# data_proV1_2.net
KiCad netlist of a schematic drawn in EAGLE
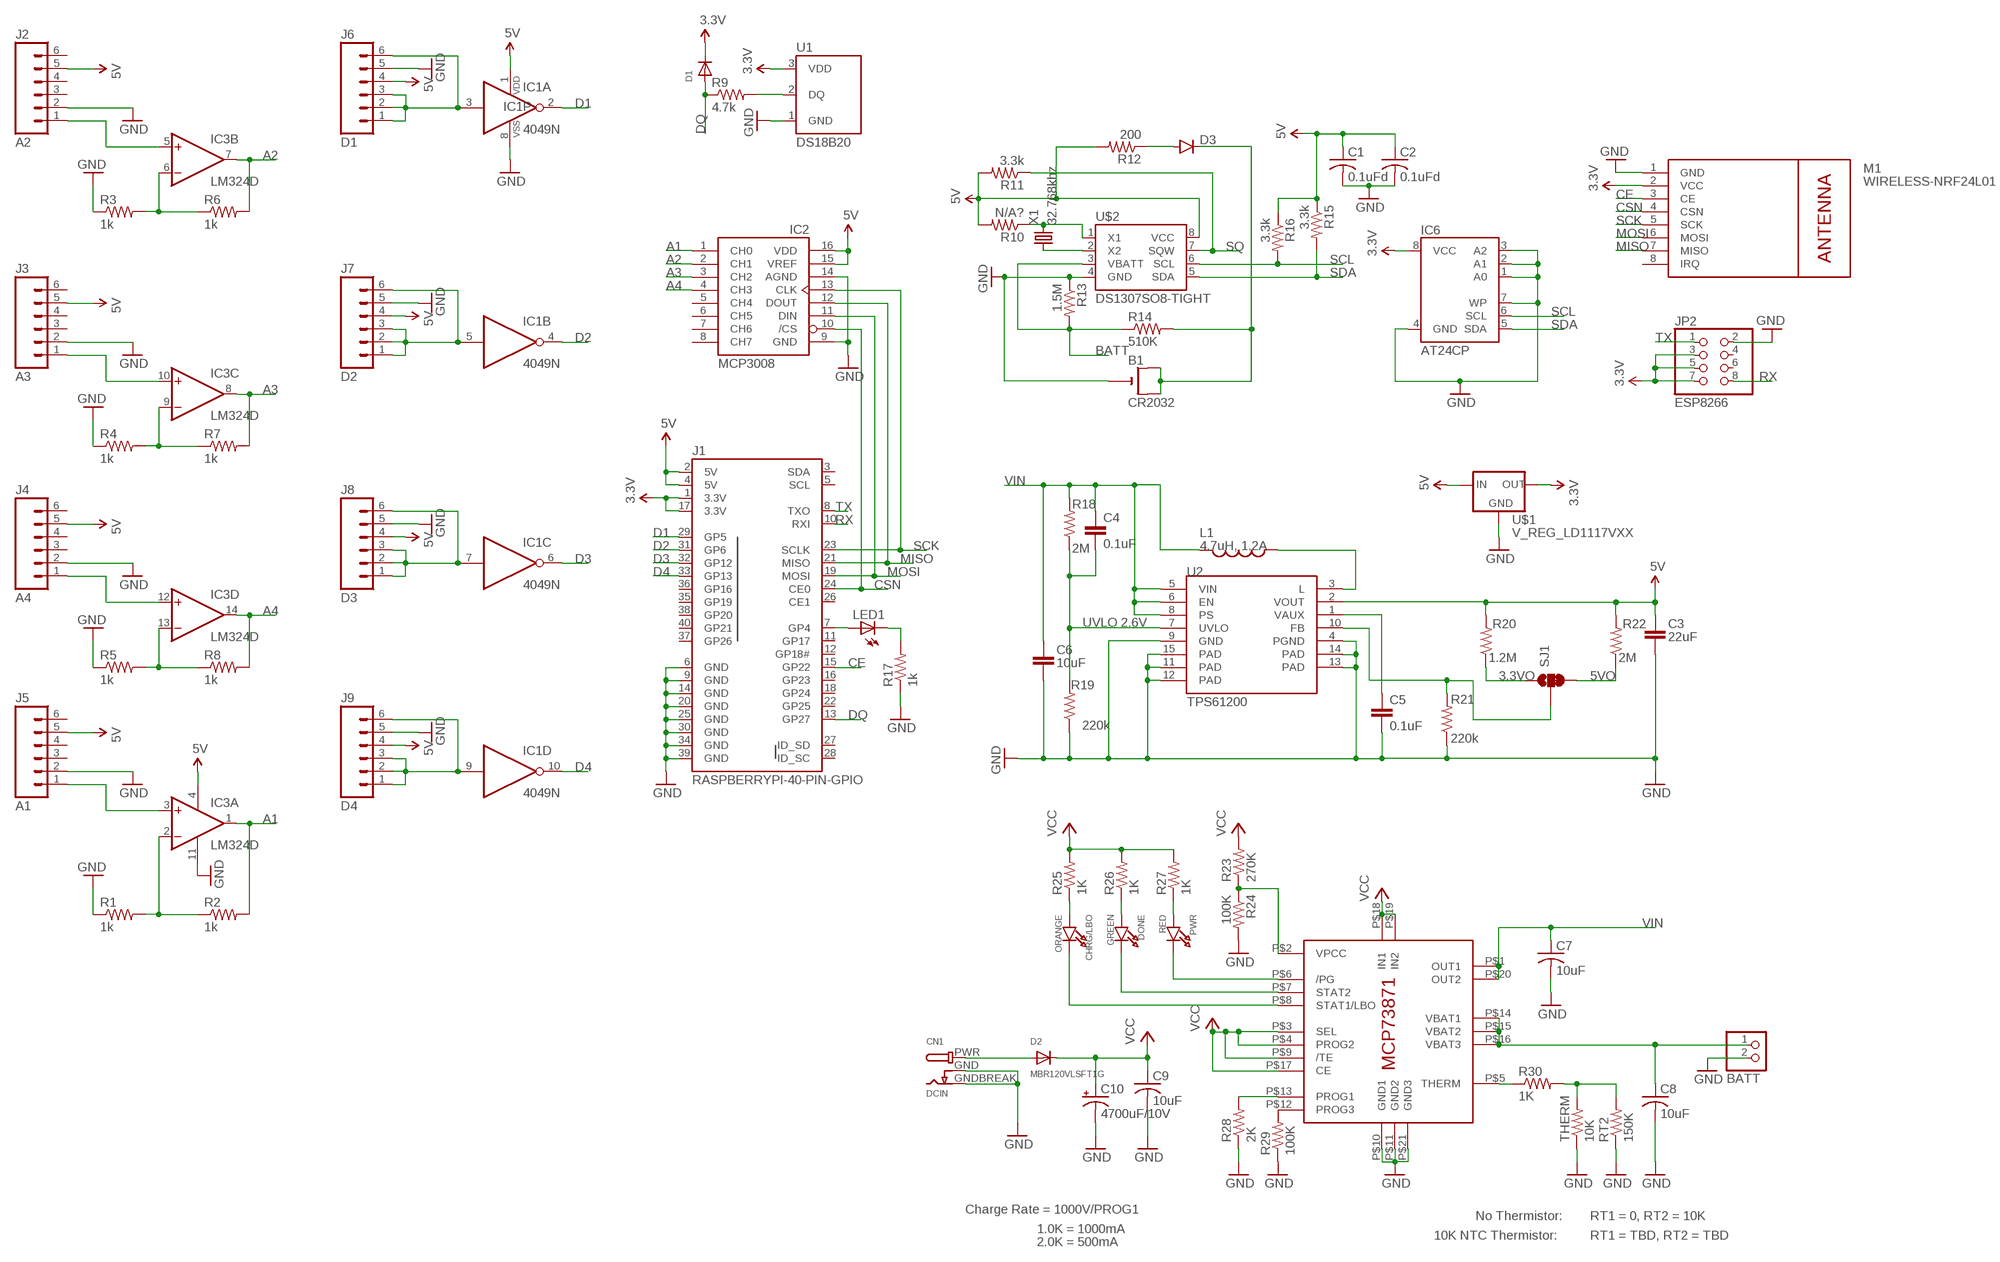
[diagram p0: schematic, sheet 1]

(export (version "E")
  (design (tool "Eeschema 10.0.6"))
  (components
    (comp (ref "B1")
      (value "CR2032")
      (footprint "eagle-import:CR2032-SMD")
      (libsource (lib "eagle-import") (part "CR2032SMT"))
    )
    (comp (ref "BATT")
      (value "JST_2PIN-SMT-RA")
      (footprint "eagle-import:JST-PH-2-SMT-RA")
      (libsource (lib "eagle-import") (part "JST_2PIN-SMT-RA"))
    )
    (comp (ref "C1")
      (value "0.1uFd")
      (footprint "eagle-import:C0805")
      (libsource (lib "eagle-import") (part "resistor_C-USC0805"))
    )
    (comp (ref "C2")
      (value "0.1uFd")
      (footprint "eagle-import:C0805")
      (libsource (lib "eagle-import") (part "resistor_C-USC0805"))
    )
    (comp (ref "C3")
      (value "22uF")
      (footprint "eagle-import:0805")
      (libsource (lib "eagle-import") (part "CAP0805"))
    )
    (comp (ref "C4")
      (value "0.1uF")
      (footprint "eagle-import:0603-CAP")
      (libsource (lib "eagle-import") (part "CAP0603-CAP"))
    )
    (comp (ref "C5")
      (value "0.1uF")
      (footprint "eagle-import:0603-CAP")
      (libsource (lib "eagle-import") (part "CAP0603-CAP"))
    )
    (comp (ref "C6")
      (value "10uF")
      (footprint "eagle-import:1206")
      (libsource (lib "eagle-import") (part "CAP1206"))
    )
    (comp (ref "C7")
      (value "10uF")
      (footprint "eagle-import:C0805K")
      (libsource (lib "eagle-import") (part "C-USC0805K"))
    )
    (comp (ref "C8")
      (value "10uF")
      (footprint "eagle-import:C0805K")
      (libsource (lib "eagle-import") (part "C-USC0805K"))
    )
    (comp (ref "C9")
      (value "10uF")
      (footprint "eagle-import:C0805K")
      (libsource (lib "eagle-import") (part "C-USC0805K"))
    )
    (comp (ref "C10")
      (value "4700uF/10V")
      (footprint "eagle-import:E5-13")
      (libsource (lib "eagle-import") (part "CPOL-USE5-13"))
    )
    (comp (ref "CHRG/LBO")
      (value "ORANGE")
      (footprint "eagle-import:CHIPLED_0805_NOOUTLINE")
      (libsource (lib "eagle-import") (part "LED0805_NOOUTLINE"))
    )
    (comp (ref "CN1")
      (value "DCIN")
      (footprint "eagle-import:DCJACK_2MM_SMT")
      (libsource (lib "eagle-import") (part "DCBARRELSMT"))
    )
    (comp (ref "D1")
      (value "DIODESOD-323F")
      (footprint "eagle-import:SOD-323F")
      (libsource (lib "eagle-import") (part "DIODESOD-323F"))
    )
    (comp (ref "D2")
      (value "MBR120VLSFT1G")
      (footprint "eagle-import:SOD-123")
      (libsource (lib "eagle-import") (part "microbuilder_DIODESOD-123"))
    )
    (comp (ref "D3")
      (value "DIODESMB")
      (footprint "eagle-import:SMB-DIODE")
      (libsource (lib "eagle-import") (part "DIODESMB"))
    )
    (comp (ref "DONE")
      (value "GREEN")
      (footprint "eagle-import:CHIPLED_0805_NOOUTLINE")
      (libsource (lib "eagle-import") (part "LED0805_NOOUTLINE"))
    )
    (comp (ref "IC1")
      (value "4049N")
      (footprint "eagle-import:DIL16")
      (libsource (lib "eagle-import") (part "4049N"))
    )
    (comp (ref "IC2")
      (value "MCP3008")
      (footprint "eagle-import:DIL16")
      (libsource (lib "eagle-import") (part "MCP3008"))
    )
    (comp (ref "IC3")
      (value "LM324D")
      (footprint "eagle-import:SO14")
      (libsource (lib "eagle-import") (part "LM324D"))
    )
    (comp (ref "IC4")
      (value "MCP73871")
      (footprint "eagle-import:QFN20_4MM")
      (libsource (lib "eagle-import") (part "MCP73871"))
    )
    (comp (ref "IC6")
      (value "AT24CP")
      (footprint "eagle-import:DIL08")
      (fields (field (name "MPN") "AT24C1024BW-SH-B"))
      (libsource (lib "eagle-import") (part "AT24CP"))
    )
    (comp (ref "J1")
      (value "RASPBERRYPI-40-PIN-GPIO")
      (footprint "eagle-import:2X20-SHROUDED")
      (libsource (lib "eagle-import") (part "RASPBERRYPI-40-PIN-GPIO"))
    )
    (comp (ref "J2")
      (value "A2")
      (footprint "eagle-import:BTA")
      (libsource (lib "eagle-import") (part "M06VERNIER-ANALOG"))
    )
    (comp (ref "J3")
      (value "A3")
      (footprint "eagle-import:BTA")
      (libsource (lib "eagle-import") (part "M06VERNIER-ANALOG"))
    )
    (comp (ref "J4")
      (value "A4")
      (footprint "eagle-import:BTA")
      (libsource (lib "eagle-import") (part "M06VERNIER-ANALOG"))
    )
    (comp (ref "J5")
      (value "A1")
      (footprint "eagle-import:BTA")
      (libsource (lib "eagle-import") (part "M06VERNIER-ANALOG"))
    )
    (comp (ref "J6")
      (value "D1")
      (footprint "eagle-import:BTD")
      (libsource (lib "eagle-import") (part "M06VERNIER-DIGITAL"))
    )
    (comp (ref "J7")
      (value "D2")
      (footprint "eagle-import:BTD")
      (libsource (lib "eagle-import") (part "M06VERNIER-DIGITAL"))
    )
    (comp (ref "J8")
      (value "D3")
      (footprint "eagle-import:BTD")
      (libsource (lib "eagle-import") (part "M06VERNIER-DIGITAL"))
    )
    (comp (ref "J9")
      (value "D4")
      (footprint "eagle-import:BTD")
      (libsource (lib "eagle-import") (part "M06VERNIER-DIGITAL"))
    )
    (comp (ref "JP2")
      (value "ESP8266")
      (footprint "eagle-import:2X04")
      (libsource (lib "eagle-import") (part "PINHD-2X4"))
    )
    (comp (ref "L1")
      (value "4.7uH, 1.2A")
      (footprint "eagle-import:CDRH2D09")
      (libsource (lib "eagle-import") (part "INDUCTOR."))
    )
    (comp (ref "LED1")
      (value "LEDCHIP-LED0805")
      (footprint "eagle-import:CHIP-LED0805")
      (libsource (lib "eagle-import") (part "LEDCHIP-LED0805"))
    )
    (comp (ref "M1")
      (value "WIRELESS-NRF24L01")
      (footprint "eagle-import:WIRELESS-NRF24L01")
      (libsource (lib "eagle-import") (part "WIRELESS-NRF24L01"))
    )
    (comp (ref "PWR")
      (value "RED")
      (footprint "eagle-import:CHIPLED_0805_NOOUTLINE")
      (libsource (lib "eagle-import") (part "LED0805_NOOUTLINE"))
    )
    (comp (ref "R1")
      (value "1k")
      (footprint "eagle-import:R0805")
      (libsource (lib "eagle-import") (part "resistor_R-US_R0805"))
    )
    (comp (ref "R2")
      (value "1k")
      (footprint "eagle-import:R0805")
      (libsource (lib "eagle-import") (part "resistor_R-US_R0805"))
    )
    (comp (ref "R3")
      (value "1k")
      (footprint "eagle-import:R0805")
      (libsource (lib "eagle-import") (part "resistor_R-US_R0805"))
    )
    (comp (ref "R4")
      (value "1k")
      (footprint "eagle-import:R0805")
      (libsource (lib "eagle-import") (part "resistor_R-US_R0805"))
    )
    (comp (ref "R5")
      (value "1k")
      (footprint "eagle-import:R0805")
      (libsource (lib "eagle-import") (part "resistor_R-US_R0805"))
    )
    (comp (ref "R6")
      (value "1k")
      (footprint "eagle-import:R0805")
      (libsource (lib "eagle-import") (part "resistor_R-US_R0805"))
    )
    (comp (ref "R7")
      (value "1k")
      (footprint "eagle-import:R0805")
      (libsource (lib "eagle-import") (part "resistor_R-US_R0805"))
    )
    (comp (ref "R8")
      (value "1k")
      (footprint "eagle-import:R0805")
      (libsource (lib "eagle-import") (part "resistor_R-US_R0805"))
    )
    (comp (ref "R9")
      (value "4.7k")
      (footprint "eagle-import:R0805")
      (libsource (lib "eagle-import") (part "resistor_R-US_R0805"))
    )
    (comp (ref "R10")
      (value "N/A?")
      (footprint "eagle-import:R0805")
      (libsource (lib "eagle-import") (part "R-US_R0805"))
    )
    (comp (ref "R11")
      (value "3.3k")
      (footprint "eagle-import:R0805")
      (libsource (lib "eagle-import") (part "R-US_R0805"))
    )
    (comp (ref "R12")
      (value "200")
      (footprint "eagle-import:R0805")
      (libsource (lib "eagle-import") (part "R-US_R0805"))
    )
    (comp (ref "R13")
      (value "1.5M")
      (footprint "eagle-import:R0805")
      (libsource (lib "eagle-import") (part "R-US_R0805"))
    )
    (comp (ref "R14")
      (value "510K")
      (footprint "eagle-import:R0805")
      (libsource (lib "eagle-import") (part "R-US_R0805"))
    )
    (comp (ref "R15")
      (value "3.3k")
      (footprint "eagle-import:R0805")
      (libsource (lib "eagle-import") (part "R-US_R0805"))
    )
    (comp (ref "R16")
      (value "3.3k")
      (footprint "eagle-import:R0805")
      (libsource (lib "eagle-import") (part "R-US_R0805"))
    )
    (comp (ref "R17")
      (value "1k")
      (footprint "eagle-import:R0805")
      (libsource (lib "eagle-import") (part "R-US_R0805"))
    )
    (comp (ref "R18")
      (value "2M")
      (footprint "eagle-import:0603-RES")
      (libsource (lib "eagle-import") (part "RESISTOR0603-RES"))
    )
    (comp (ref "R19")
      (value "220k")
      (footprint "eagle-import:0603-RES")
      (libsource (lib "eagle-import") (part "RESISTOR0603-RES"))
    )
    (comp (ref "R20")
      (value "1.2M")
      (footprint "eagle-import:0603-RES")
      (libsource (lib "eagle-import") (part "RESISTOR0603-RES"))
    )
    (comp (ref "R21")
      (value "220k")
      (footprint "eagle-import:0603-RES")
      (libsource (lib "eagle-import") (part "RESISTOR0603-RES"))
    )
    (comp (ref "R22")
      (value "2M")
      (footprint "eagle-import:0603-RES")
      (libsource (lib "eagle-import") (part "RESISTOR0603-RES"))
    )
    (comp (ref "R23")
      (value "270K")
      (footprint "eagle-import:R0805")
      (libsource (lib "eagle-import") (part "R-US_R0805"))
    )
    (comp (ref "R24")
      (value "100K")
      (footprint "eagle-import:R0805")
      (libsource (lib "eagle-import") (part "R-US_R0805"))
    )
    (comp (ref "R25")
      (value "1K")
      (footprint "eagle-import:R0805")
      (libsource (lib "eagle-import") (part "R-US_R0805"))
    )
    (comp (ref "R26")
      (value "1K")
      (footprint "eagle-import:R0805")
      (libsource (lib "eagle-import") (part "R-US_R0805"))
    )
    (comp (ref "R27")
      (value "1K")
      (footprint "eagle-import:R0805")
      (libsource (lib "eagle-import") (part "R-US_R0805"))
    )
    (comp (ref "R28")
      (value "2K")
      (footprint "eagle-import:0805-THM")
      (libsource (lib "eagle-import") (part "R-US_FLIPFLOP"))
    )
    (comp (ref "R29")
      (value "100K")
      (footprint "eagle-import:R0805")
      (libsource (lib "eagle-import") (part "R-US_R0805"))
    )
    (comp (ref "R30")
      (value "1K")
      (footprint "eagle-import:M0805")
      (libsource (lib "eagle-import") (part "R-US_M0805"))
    )
    (comp (ref "RT2")
      (value "150K")
      (footprint "eagle-import:M0805")
      (libsource (lib "eagle-import") (part "R-US_M0805"))
    )
    (comp (ref "SJ1")
      (value "SOLDERJUMPER_2WAYPASTE2&3")
      (footprint "eagle-import:SJ_3_PASTE2&3")
      (libsource (lib "eagle-import") (part "SOLDERJUMPER_2WAYPASTE2&3"))
    )
    (comp (ref "THERM")
      (value "10K")
      (footprint "eagle-import:0805-THM")
      (libsource (lib "eagle-import") (part "R-US_FLIPFLOP"))
    )
    (comp (ref "U$1")
      (value "V_REG_LD1117VXX")
      (footprint "eagle-import:78XXL")
      (libsource (lib "eagle-import") (part "V_REG_LD1117VXX"))
    )
    (comp (ref "U$2")
      (value "DS1307SO8-TIGHT")
      (footprint "eagle-import:SO08-TIGHT")
      (libsource (lib "eagle-import") (part "DS1307SO8-TIGHT"))
    )
    (comp (ref "U1")
      (value "DS18B20")
      (footprint "eagle-import:TO-92-AMMO")
      (libsource (lib "eagle-import") (part "DS18B20"))
    )
    (comp (ref "U2")
      (value "TPS61200")
      (footprint "eagle-import:QFN-10_PAD")
      (libsource (lib "eagle-import") (part "TPS61200"))
    )
    (comp (ref "X1")
      (value "32.768khz")
      (footprint "eagle-import:TC38H")
      (libsource (lib "eagle-import") (part "CRYSTALTC38H"))
    )
  )
  (nets
    (net (code "1") (name "/3.3VO") (class "Default")
      (node (ref "R20") (pin "1") (pinfunction "1_1") (pintype "passive"))
      (node (ref "SJ1") (pin "1") (pinfunction "1_1") (pintype "passive"))
    )
    (net (code "2") (name "/5VO") (class "Default")
      (node (ref "R22") (pin "1") (pinfunction "1_1") (pintype "passive"))
      (node (ref "SJ1") (pin "3") (pinfunction "3_3") (pintype "passive"))
    )
    (net (code "3") (name "/A1") (class "Default")
      (node (ref "IC2") (pin "1") (pinfunction "CH0_1") (pintype "input"))
      (node (ref "IC3") (pin "1") (pinfunction "OUT_1") (pintype "output"))
      (node (ref "R2") (pin "2") (pinfunction "2_2") (pintype "passive"))
    )
    (net (code "4") (name "/A2") (class "Default")
      (node (ref "IC2") (pin "2") (pinfunction "CH1_2") (pintype "input"))
      (node (ref "IC3") (pin "7") (pinfunction "OUT_7") (pintype "output"))
      (node (ref "R6") (pin "2") (pinfunction "2_2") (pintype "passive"))
    )
    (net (code "5") (name "/A3") (class "Default")
      (node (ref "IC2") (pin "3") (pinfunction "CH2_3") (pintype "input"))
      (node (ref "IC3") (pin "8") (pinfunction "OUT_8") (pintype "output"))
      (node (ref "R7") (pin "2") (pinfunction "2_2") (pintype "passive"))
    )
    (net (code "6") (name "/A4") (class "Default")
      (node (ref "IC2") (pin "4") (pinfunction "CH3_4") (pintype "input"))
      (node (ref "IC3") (pin "14") (pinfunction "OUT_14") (pintype "output"))
      (node (ref "R8") (pin "2") (pinfunction "2_2") (pintype "passive"))
    )
    (net (code "7") (name "/BATT") (class "Default")
      (node (ref "R13") (pin "2") (pinfunction "2_2") (pintype "passive"))
      (node (ref "R14") (pin "1") (pinfunction "1_1") (pintype "passive"))
      (node (ref "U$2") (pin "3") (pinfunction "VBATT_3") (pintype "bidirectional"))
    )
    (net (code "8") (name "/CE") (class "Default")
      (node (ref "J1") (pin "15") (pinfunction "GP22_15") (pintype "bidirectional"))
      (node (ref "M1") (pin "3") (pinfunction "CE_3") (pintype "bidirectional"))
    )
    (net (code "9") (name "/CSN") (class "Default")
      (node (ref "IC2") (pin "10") (pinfunction "/CS_10") (pintype "input"))
      (node (ref "J1") (pin "24") (pinfunction "CE0_24") (pintype "output"))
      (node (ref "M1") (pin "4") (pinfunction "CSN_4") (pintype "bidirectional"))
    )
    (net (code "10") (name "/D1") (class "Default")
      (node (ref "IC1") (pin "2") (pinfunction "O_2") (pintype "output"))
      (node (ref "J1") (pin "29") (pinfunction "GP5_29") (pintype "bidirectional"))
    )
    (net (code "11") (name "/D2") (class "Default")
      (node (ref "IC1") (pin "4") (pinfunction "O_4") (pintype "output"))
      (node (ref "J1") (pin "31") (pinfunction "GP6_31") (pintype "bidirectional"))
    )
    (net (code "12") (name "/D3") (class "Default")
      (node (ref "IC1") (pin "6") (pinfunction "O_6") (pintype "output"))
      (node (ref "J1") (pin "32") (pinfunction "GP12_32") (pintype "bidirectional"))
    )
    (net (code "13") (name "/D4") (class "Default")
      (node (ref "IC1") (pin "10") (pinfunction "O_10") (pintype "output"))
      (node (ref "J1") (pin "33") (pinfunction "GP13_33") (pintype "bidirectional"))
    )
    (net (code "14") (name "/DQ") (class "Default")
      (node (ref "D1") (pin "A") (pinfunction "A_A") (pintype "passive"))
      (node (ref "J1") (pin "13") (pinfunction "GP27_13") (pintype "bidirectional"))
      (node (ref "R9") (pin "1") (pinfunction "1_1") (pintype "passive"))
    )
    (net (code "15") (name "/MISO") (class "Default")
      (node (ref "IC2") (pin "12") (pinfunction "DOUT_12") (pintype "output"))
      (node (ref "J1") (pin "21") (pinfunction "MISO_21") (pintype "input"))
      (node (ref "M1") (pin "7") (pinfunction "MISO_7") (pintype "bidirectional"))
    )
    (net (code "16") (name "/MOSI") (class "Default")
      (node (ref "IC2") (pin "11") (pinfunction "DIN_11") (pintype "input"))
      (node (ref "J1") (pin "19") (pinfunction "MOSI_19") (pintype "output"))
      (node (ref "M1") (pin "6") (pinfunction "MOSI_6") (pintype "bidirectional"))
    )
    (net (code "17") (name "/RX") (class "Default")
      (node (ref "J1") (pin "10") (pinfunction "RXI_10") (pintype "input"))
      (node (ref "JP2") (pin "8") (pinfunction "8_8") (pintype "passive"))
    )
    (net (code "18") (name "/SCK") (class "Default")
      (node (ref "IC2") (pin "13") (pinfunction "CLK_13") (pintype "input"))
      (node (ref "J1") (pin "23") (pinfunction "SCLK_23") (pintype "output"))
      (node (ref "M1") (pin "5") (pinfunction "SCK_5") (pintype "bidirectional"))
    )
    (net (code "19") (name "/SCL") (class "Default")
      (node (ref "IC6") (pin "6") (pinfunction "SCL_6") (pintype "bidirectional"))
      (node (ref "R16") (pin "2") (pinfunction "2_2") (pintype "passive"))
      (node (ref "U$2") (pin "6") (pinfunction "SCL_6") (pintype "bidirectional"))
    )
    (net (code "20") (name "/SDA") (class "Default")
      (node (ref "IC6") (pin "5") (pinfunction "SDA_5") (pintype "bidirectional"))
      (node (ref "R15") (pin "2") (pinfunction "2_2") (pintype "passive"))
      (node (ref "U$2") (pin "5") (pinfunction "SDA_5") (pintype "bidirectional"))
    )
    (net (code "21") (name "/SQ") (class "Default")
      (node (ref "R11") (pin "1") (pinfunction "1_1") (pintype "passive"))
      (node (ref "U$2") (pin "7") (pinfunction "SQW_7") (pintype "bidirectional"))
    )
    (net (code "22") (name "/TX") (class "Default")
      (node (ref "J1") (pin "8") (pinfunction "TXO_8") (pintype "output"))
      (node (ref "JP2") (pin "1") (pinfunction "1_1") (pintype "passive"))
    )
    (net (code "23") (name "/VIN") (class "Default")
      (node (ref "C4") (pin "1") (pinfunction "1_1") (pintype "passive"))
      (node (ref "C6") (pin "1") (pinfunction "1_1") (pintype "passive"))
      (node (ref "C7") (pin "1") (pinfunction "1_1") (pintype "passive"))
      (node (ref "IC4") (pin "P$1") (pinfunction "OUT1_P$1") (pintype "output"))
      (node (ref "IC4") (pin "P$20") (pinfunction "OUT2_P$20") (pintype "output"))
      (node (ref "L1") (pin "P$2") (pinfunction "2_P$2") (pintype "passive"))
      (node (ref "R18") (pin "2") (pinfunction "2_2") (pintype "passive"))
      (node (ref "U2") (pin "5") (pinfunction "VIN_5") (pintype "power_in"))
      (node (ref "U2") (pin "6") (pinfunction "EN_6") (pintype "input"))
      (node (ref "U2") (pin "8") (pinfunction "PS_8") (pintype "input"))
    )
    (net (code "24") (name "3.3V") (class "Default")
      (node (ref "D1") (pin "C") (pinfunction "C_C") (pintype "passive"))
      (node (ref "IC6") (pin "8") (pinfunction "VCC_8") (pintype "power_in"))
      (node (ref "J1") (pin "1") (pinfunction "3.3V_1") (pintype "power_in"))
      (node (ref "J1") (pin "17") (pinfunction "3.3V_17") (pintype "power_in"))
      (node (ref "JP2") (pin "3") (pinfunction "3_3") (pintype "passive"))
      (node (ref "JP2") (pin "5") (pinfunction "5_5") (pintype "passive"))
      (node (ref "JP2") (pin "7") (pinfunction "7_7") (pintype "passive"))
      (node (ref "M1") (pin "2") (pinfunction "VCC_2") (pintype "power_in"))
      (node (ref "U$1") (pin "GND") (pinfunction "OUT_GND") (pintype "passive"))
      (node (ref "U1") (pin "3") (pinfunction "VDD_3") (pintype "power_in"))
    )
    (net (code "25") (name "5V") (class "Default")
      (node (ref "C1") (pin "1") (pinfunction "1_1") (pintype "passive"))
      (node (ref "C2") (pin "1") (pinfunction "1_1") (pintype "passive"))
      (node (ref "C3") (pin "1") (pinfunction "1_1") (pintype "passive"))
      (node (ref "IC1") (pin "1") (pinfunction "VDD_1") (pintype "power_in"))
      (node (ref "IC2") (pin "15") (pinfunction "VREF_15") (pintype "input"))
      (node (ref "IC2") (pin "16") (pinfunction "VDD_16") (pintype "power_in"))
      (node (ref "IC3") (pin "4") (pinfunction "V+_4") (pintype "power_in"))
      (node (ref "J1") (pin "2") (pinfunction "5V_2") (pintype "power_in"))
      (node (ref "J1") (pin "4") (pinfunction "5V_4") (pintype "power_in"))
      (node (ref "J2") (pin "5") (pinfunction "5_5") (pintype "passive"))
      (node (ref "J3") (pin "5") (pinfunction "5_5") (pintype "passive"))
      (node (ref "J4") (pin "5") (pinfunction "5_5") (pintype "passive"))
      (node (ref "J5") (pin "5") (pinfunction "5_5") (pintype "passive"))
      (node (ref "J6") (pin "4") (pinfunction "4_4") (pintype "passive"))
      (node (ref "J7") (pin "4") (pinfunction "4_4") (pintype "passive"))
      (node (ref "J8") (pin "4") (pinfunction "4_4") (pintype "passive"))
      (node (ref "J9") (pin "4") (pinfunction "4_4") (pintype "passive"))
      (node (ref "R10") (pin "2") (pinfunction "2_2") (pintype "passive"))
      (node (ref "R11") (pin "2") (pinfunction "2_2") (pintype "passive"))
      (node (ref "R12") (pin "2") (pinfunction "2_2") (pintype "passive"))
      (node (ref "R15") (pin "1") (pinfunction "1_1") (pintype "passive"))
      (node (ref "R16") (pin "1") (pinfunction "1_1") (pintype "passive"))
      (node (ref "R20") (pin "2") (pinfunction "2_2") (pintype "passive"))
      (node (ref "R22") (pin "2") (pinfunction "2_2") (pintype "passive"))
      (node (ref "U$1") (pin "OUT") (pinfunction "IN_OUT") (pintype "input"))
      (node (ref "U$2") (pin "8") (pinfunction "VCC_8") (pintype "bidirectional"))
      (node (ref "U2") (pin "2") (pinfunction "VOUT_2") (pintype "passive"))
    )
    (net (code "26") (name "GND") (class "Default")
      (node (ref "B1") (pin "-") (pinfunction "-_-") (pintype "passive"))
      (node (ref "BATT") (pin "2") (pinfunction "1_2") (pintype "passive"))
      (node (ref "C1") (pin "2") (pinfunction "2_2") (pintype "passive"))
      (node (ref "C10") (pin "-") (pinfunction "-_-") (pintype "passive"))
      (node (ref "C2") (pin "2") (pinfunction "2_2") (pintype "passive"))
      (node (ref "C3") (pin "2") (pinfunction "2_2") (pintype "passive"))
      (node (ref "C5") (pin "2") (pinfunction "2_2") (pintype "passive"))
      (node (ref "C6") (pin "2") (pinfunction "2_2") (pintype "passive"))
      (node (ref "C7") (pin "2") (pinfunction "2_2") (pintype "passive"))
      (node (ref "C8") (pin "2") (pinfunction "2_2") (pintype "passive"))
      (node (ref "C9") (pin "2") (pinfunction "2_2") (pintype "passive"))
      (node (ref "CN1") (pin "GND") (pinfunction "GNDBREAK_GND") (pintype "power_in"))
      (node (ref "CN1") (pin "GNDBREAK") (pinfunction "GND_GNDBREAK") (pintype "power_in"))
      (node (ref "IC1") (pin "8") (pinfunction "VSS_8") (pintype "power_in"))
      (node (ref "IC2") (pin "14") (pinfunction "AGND_14") (pintype "power_in"))
      (node (ref "IC2") (pin "9") (pinfunction "GND_9") (pintype "power_in"))
      (node (ref "IC3") (pin "11") (pinfunction "V-_11") (pintype "power_in"))
      (node (ref "IC4") (pin "P$10") (pinfunction "GND1_P$10") (pintype "power_in"))
      (node (ref "IC4") (pin "P$11") (pinfunction "GND2_P$11") (pintype "power_in"))
      (node (ref "IC4") (pin "P$21") (pinfunction "GND3_P$21") (pintype "power_in"))
      (node (ref "IC6") (pin "1") (pinfunction "A0_1") (pintype "input"))
      (node (ref "IC6") (pin "2") (pinfunction "A1_2") (pintype "input"))
      (node (ref "IC6") (pin "3") (pinfunction "A2_3") (pintype "input"))
      (node (ref "IC6") (pin "4") (pinfunction "GND_4") (pintype "power_in"))
      (node (ref "IC6") (pin "7") (pinfunction "WP_7") (pintype "input"))
      (node (ref "J1") (pin "14") (pinfunction "GND_14") (pintype "power_in"))
      (node (ref "J1") (pin "20") (pinfunction "GND_20") (pintype "power_in"))
      (node (ref "J1") (pin "25") (pinfunction "GND_25") (pintype "power_in"))
      (node (ref "J1") (pin "30") (pinfunction "GND_30") (pintype "power_in"))
      (node (ref "J1") (pin "34") (pinfunction "GND_34") (pintype "power_in"))
      (node (ref "J1") (pin "39") (pinfunction "GND_39") (pintype "power_in"))
      (node (ref "J1") (pin "6") (pinfunction "GND_6") (pintype "power_in"))
      (node (ref "J1") (pin "9") (pinfunction "GND_9") (pintype "power_in"))
      (node (ref "J2") (pin "2") (pinfunction "2_2") (pintype "passive"))
      (node (ref "J3") (pin "2") (pinfunction "2_2") (pintype "passive"))
      (node (ref "J4") (pin "2") (pinfunction "2_2") (pintype "passive"))
      (node (ref "J5") (pin "2") (pinfunction "2_2") (pintype "passive"))
      (node (ref "J6") (pin "5") (pinfunction "5_5") (pintype "passive"))
      (node (ref "J7") (pin "5") (pinfunction "5_5") (pintype "passive"))
      (node (ref "J8") (pin "5") (pinfunction "5_5") (pintype "passive"))
      (node (ref "J9") (pin "5") (pinfunction "5_5") (pintype "passive"))
      (node (ref "JP2") (pin "2") (pinfunction "2_2") (pintype "passive"))
      (node (ref "M1") (pin "1") (pinfunction "GND_1") (pintype "power_in"))
      (node (ref "R1") (pin "1") (pinfunction "1_1") (pintype "passive"))
      (node (ref "R13") (pin "1") (pinfunction "1_1") (pintype "passive"))
      (node (ref "R17") (pin "1") (pinfunction "1_1") (pintype "passive"))
      (node (ref "R19") (pin "1") (pinfunction "1_1") (pintype "passive"))
      (node (ref "R21") (pin "1") (pinfunction "1_1") (pintype "passive"))
      (node (ref "R24") (pin "2") (pinfunction "2_2") (pintype "passive"))
      (node (ref "R28") (pin "1") (pinfunction "1_1") (pintype "passive"))
      (node (ref "R29") (pin "1") (pinfunction "1_1") (pintype "passive"))
      (node (ref "R3") (pin "1") (pinfunction "1_1") (pintype "passive"))
      (node (ref "R4") (pin "1") (pinfunction "1_1") (pintype "passive"))
      (node (ref "R5") (pin "1") (pinfunction "1_1") (pintype "passive"))
      (node (ref "RT2") (pin "1") (pinfunction "1_1") (pintype "passive"))
      (node (ref "THERM") (pin "1") (pinfunction "1_1") (pintype "passive"))
      (node (ref "U$1") (pin "IN") (pinfunction "GND_IN") (pintype "input"))
      (node (ref "U$2") (pin "4") (pinfunction "GND_4") (pintype "bidirectional"))
      (node (ref "U1") (pin "1") (pinfunction "GND_1") (pintype "power_in"))
      (node (ref "U2") (pin "11") (pinfunction "PAD_11") (pintype "power_in"))
      (node (ref "U2") (pin "12") (pinfunction "PAD_12") (pintype "power_in"))
      (node (ref "U2") (pin "13") (pinfunction "PAD_13") (pintype "power_in"))
      (node (ref "U2") (pin "14") (pinfunction "PAD_14") (pintype "power_in"))
      (node (ref "U2") (pin "15") (pinfunction "PAD_15") (pintype "power_in"))
      (node (ref "U2") (pin "4") (pinfunction "PGND_4") (pintype "power_in"))
      (node (ref "U2") (pin "9") (pinfunction "GND_9") (pintype "power_in"))
    )
    (net (code "27") (name "Net-(B1-+)") (class "Default")
      (node (ref "B1") (pin "+$1") (pinfunction "+_+$1") (pintype "passive"))
      (node (ref "B1") (pin "+$2") (pinfunction "+1_+$2") (pintype "passive"))
      (node (ref "D3") (pin "C") (pinfunction "C_C") (pintype "passive"))
      (node (ref "R14") (pin "2") (pinfunction "2_2") (pintype "passive"))
    )
    (net (code "28") (name "Net-(BATT-2)") (class "Default")
      (node (ref "BATT") (pin "1") (pinfunction "2_1") (pintype "passive"))
      (node (ref "C8") (pin "1") (pinfunction "1_1") (pintype "passive"))
      (node (ref "IC4") (pin "P$14") (pinfunction "VBAT1_P$14") (pintype "output"))
      (node (ref "IC4") (pin "P$15") (pinfunction "VBAT2_P$15") (pintype "output"))
      (node (ref "IC4") (pin "P$16") (pinfunction "VBAT3_P$16") (pintype "output"))
    )
    (net (code "29") (name "Net-(CHRG/LBO-PadA)") (class "Default")
      (node (ref "CHRG/LBO") (pin "A") (pinfunction "A_A") (pintype "passive"))
      (node (ref "R25") (pin "1") (pinfunction "1_1") (pintype "passive"))
    )
    (net (code "30") (name "Net-(CN1-PadPWR)") (class "Default")
      (node (ref "CN1") (pin "PWR") (pinfunction "PWR_PWR") (pintype "power_in"))
      (node (ref "D2") (pin "A") (pinfunction "A_A") (pintype "passive"))
    )
    (net (code "31") (name "Net-(D3-PadA)") (class "Default")
      (node (ref "D3") (pin "A") (pinfunction "A_A") (pintype "passive"))
      (node (ref "R12") (pin "1") (pinfunction "1_1") (pintype "passive"))
    )
    (net (code "32") (name "Net-(DONE-PadA)") (class "Default")
      (node (ref "DONE") (pin "A") (pinfunction "A_A") (pintype "passive"))
      (node (ref "R26") (pin "1") (pinfunction "1_1") (pintype "passive"))
    )
    (net (code "33") (name "Net-(IC1A-I)") (class "Default")
      (node (ref "IC1") (pin "3") (pinfunction "I_3") (pintype "input"))
      (node (ref "J6") (pin "1") (pinfunction "1_1") (pintype "passive"))
      (node (ref "J6") (pin "2") (pinfunction "2_2") (pintype "passive"))
      (node (ref "J6") (pin "3") (pinfunction "3_3") (pintype "passive"))
      (node (ref "J6") (pin "6") (pinfunction "6_6") (pintype "passive"))
    )
    (net (code "34") (name "Net-(IC1B-I)") (class "Default")
      (node (ref "IC1") (pin "5") (pinfunction "I_5") (pintype "input"))
      (node (ref "J7") (pin "1") (pinfunction "1_1") (pintype "passive"))
      (node (ref "J7") (pin "2") (pinfunction "2_2") (pintype "passive"))
      (node (ref "J7") (pin "3") (pinfunction "3_3") (pintype "passive"))
      (node (ref "J7") (pin "6") (pinfunction "6_6") (pintype "passive"))
    )
    (net (code "35") (name "Net-(IC1C-I)") (class "Default")
      (node (ref "IC1") (pin "7") (pinfunction "I_7") (pintype "input"))
      (node (ref "J8") (pin "1") (pinfunction "1_1") (pintype "passive"))
      (node (ref "J8") (pin "2") (pinfunction "2_2") (pintype "passive"))
      (node (ref "J8") (pin "3") (pinfunction "3_3") (pintype "passive"))
      (node (ref "J8") (pin "6") (pinfunction "6_6") (pintype "passive"))
    )
    (net (code "36") (name "Net-(IC1D-I)") (class "Default")
      (node (ref "IC1") (pin "9") (pinfunction "I_9") (pintype "input"))
      (node (ref "J9") (pin "1") (pinfunction "1_1") (pintype "passive"))
      (node (ref "J9") (pin "2") (pinfunction "2_2") (pintype "passive"))
      (node (ref "J9") (pin "3") (pinfunction "3_3") (pintype "passive"))
      (node (ref "J9") (pin "6") (pinfunction "6_6") (pintype "passive"))
    )
    (net (code "37") (name "Net-(IC3A-+IN)") (class "Default")
      (node (ref "IC3") (pin "3") (pinfunction "+IN_3") (pintype "input"))
      (node (ref "J5") (pin "1") (pinfunction "1_1") (pintype "passive"))
    )
    (net (code "38") (name "Net-(IC3A--IN)") (class "Default")
      (node (ref "IC3") (pin "2") (pinfunction "-IN_2") (pintype "input"))
      (node (ref "R1") (pin "2") (pinfunction "2_2") (pintype "passive"))
      (node (ref "R2") (pin "1") (pinfunction "1_1") (pintype "passive"))
    )
    (net (code "39") (name "Net-(IC3B-+IN)") (class "Default")
      (node (ref "IC3") (pin "5") (pinfunction "+IN_5") (pintype "input"))
      (node (ref "J2") (pin "1") (pinfunction "1_1") (pintype "passive"))
    )
    (net (code "40") (name "Net-(IC3B--IN)") (class "Default")
      (node (ref "IC3") (pin "6") (pinfunction "-IN_6") (pintype "input"))
      (node (ref "R3") (pin "2") (pinfunction "2_2") (pintype "passive"))
      (node (ref "R6") (pin "1") (pinfunction "1_1") (pintype "passive"))
    )
    (net (code "41") (name "Net-(IC3C-+IN)") (class "Default")
      (node (ref "IC3") (pin "10") (pinfunction "+IN_10") (pintype "input"))
      (node (ref "J3") (pin "1") (pinfunction "1_1") (pintype "passive"))
    )
    (net (code "42") (name "Net-(IC3C--IN)") (class "Default")
      (node (ref "IC3") (pin "9") (pinfunction "-IN_9") (pintype "input"))
      (node (ref "R4") (pin "2") (pinfunction "2_2") (pintype "passive"))
      (node (ref "R7") (pin "1") (pinfunction "1_1") (pintype "passive"))
    )
    (net (code "43") (name "Net-(IC3D-+IN)") (class "Default")
      (node (ref "IC3") (pin "12") (pinfunction "+IN_12") (pintype "input"))
      (node (ref "J4") (pin "1") (pinfunction "1_1") (pintype "passive"))
    )
    (net (code "44") (name "Net-(IC3D--IN)") (class "Default")
      (node (ref "IC3") (pin "13") (pinfunction "-IN_13") (pintype "input"))
      (node (ref "R5") (pin "2") (pinfunction "2_2") (pintype "passive"))
      (node (ref "R8") (pin "1") (pinfunction "1_1") (pintype "passive"))
    )
    (net (code "45") (name "Net-(IC4-PROG1)") (class "Default")
      (node (ref "IC4") (pin "P$13") (pinfunction "PROG1_P$13") (pintype "input"))
      (node (ref "R28") (pin "2") (pinfunction "2_2") (pintype "passive"))
    )
    (net (code "46") (name "Net-(IC4-PROG3)") (class "Default")
      (node (ref "IC4") (pin "P$12") (pinfunction "PROG3_P$12") (pintype "input"))
      (node (ref "R29") (pin "2") (pinfunction "2_2") (pintype "passive"))
    )
    (net (code "47") (name "Net-(IC4-STAT1{slash}LBO)") (class "Default")
      (node (ref "CHRG/LBO") (pin "C") (pinfunction "C_C") (pintype "passive"))
      (node (ref "IC4") (pin "P$8") (pinfunction "STAT1/LBO_P$8") (pintype "output"))
    )
    (net (code "48") (name "Net-(IC4-STAT2)") (class "Default")
      (node (ref "DONE") (pin "C") (pinfunction "C_C") (pintype "passive"))
      (node (ref "IC4") (pin "P$7") (pinfunction "STAT2_P$7") (pintype "output"))
    )
    (net (code "49") (name "Net-(IC4-THERM)") (class "Default")
      (node (ref "IC4") (pin "P$5") (pinfunction "THERM_P$5") (pintype "input"))
      (node (ref "R30") (pin "1") (pinfunction "1_1") (pintype "passive"))
    )
    (net (code "50") (name "Net-(IC4-VPCC)") (class "Default")
      (node (ref "IC4") (pin "P$2") (pinfunction "VPCC_P$2") (pintype "input"))
      (node (ref "R23") (pin "1") (pinfunction "1_1") (pintype "passive"))
      (node (ref "R24") (pin "1") (pinfunction "1_1") (pintype "passive"))
    )
    (net (code "51") (name "Net-(IC4-{slash}PG)") (class "Default")
      (node (ref "IC4") (pin "P$6") (pinfunction "/PG_P$6") (pintype "output"))
      (node (ref "PWR") (pin "C") (pinfunction "C_C") (pintype "passive"))
    )
    (net (code "52") (name "Net-(J1-GP4)") (class "Default")
      (node (ref "J1") (pin "7") (pinfunction "GP4_7") (pintype "bidirectional"))
      (node (ref "LED1") (pin "A") (pinfunction "A_A") (pintype "passive"))
    )
    (net (code "53") (name "Net-(L1-1)") (class "Default")
      (node (ref "L1") (pin "P$1") (pinfunction "1_P$1") (pintype "passive"))
      (node (ref "U2") (pin "3") (pinfunction "L_3") (pintype "passive"))
    )
    (net (code "54") (name "Net-(LED1-PadC)") (class "Default")
      (node (ref "LED1") (pin "C") (pinfunction "C_C") (pintype "passive"))
      (node (ref "R17") (pin "2") (pinfunction "2_2") (pintype "passive"))
    )
    (net (code "55") (name "Net-(PWR-PadA)") (class "Default")
      (node (ref "PWR") (pin "A") (pinfunction "A_A") (pintype "passive"))
      (node (ref "R27") (pin "1") (pinfunction "1_1") (pintype "passive"))
    )
    (net (code "56") (name "Net-(R30-Pad2)") (class "Default")
      (node (ref "R30") (pin "2") (pinfunction "2_2") (pintype "passive"))
      (node (ref "RT2") (pin "2") (pinfunction "2_2") (pintype "passive"))
      (node (ref "THERM") (pin "2") (pinfunction "2_2") (pintype "passive"))
    )
    (net (code "57") (name "Net-(U$2-X1)") (class "Default")
      (node (ref "R10") (pin "1") (pinfunction "1_1") (pintype "passive"))
      (node (ref "U$2") (pin "1") (pinfunction "X1_1") (pintype "bidirectional"))
      (node (ref "X1") (pin "2") (pinfunction "2_2") (pintype "passive"))
    )
    (net (code "58") (name "Net-(U$2-X2)") (class "Default")
      (node (ref "U$2") (pin "2") (pinfunction "X2_2") (pintype "bidirectional"))
      (node (ref "X1") (pin "1") (pinfunction "1_1") (pintype "passive"))
    )
    (net (code "59") (name "Net-(U1-DQ)") (class "Default")
      (node (ref "R9") (pin "2") (pinfunction "2_2") (pintype "passive"))
      (node (ref "U1") (pin "2") (pinfunction "DQ_2") (pintype "bidirectional"))
    )
    (net (code "60") (name "Net-(U2-FB)") (class "Default")
      (node (ref "R21") (pin "2") (pinfunction "2_2") (pintype "passive"))
      (node (ref "SJ1") (pin "2") (pinfunction "2_2") (pintype "passive"))
      (node (ref "U2") (pin "10") (pinfunction "FB_10") (pintype "passive"))
    )
    (net (code "61") (name "Net-(U2-UVLO)") (class "Default")
      (node (ref "C4") (pin "2") (pinfunction "2_2") (pintype "passive"))
      (node (ref "R18") (pin "1") (pinfunction "1_1") (pintype "passive"))
      (node (ref "R19") (pin "2") (pinfunction "2_2") (pintype "passive"))
      (node (ref "U2") (pin "7") (pinfunction "UVLO_7") (pintype "passive"))
    )
    (net (code "62") (name "Net-(U2-VAUX)") (class "Default")
      (node (ref "C5") (pin "1") (pinfunction "1_1") (pintype "passive"))
      (node (ref "U2") (pin "1") (pinfunction "VAUX_1") (pintype "passive"))
    )
    (net (code "63") (name "VCC") (class "Default")
      (node (ref "C10") (pin "+") (pinfunction "+_+") (pintype "passive"))
      (node (ref "C9") (pin "1") (pinfunction "1_1") (pintype "passive"))
      (node (ref "D2") (pin "C") (pinfunction "C_C") (pintype "passive"))
      (node (ref "IC4") (pin "P$17") (pinfunction "CE_P$17") (pintype "input"))
      (node (ref "IC4") (pin "P$18") (pinfunction "IN1_P$18") (pintype "input"))
      (node (ref "IC4") (pin "P$19") (pinfunction "IN2_P$19") (pintype "input"))
      (node (ref "IC4") (pin "P$3") (pinfunction "SEL_P$3") (pintype "input"))
      (node (ref "IC4") (pin "P$4") (pinfunction "PROG2_P$4") (pintype "input"))
      (node (ref "IC4") (pin "P$9") (pinfunction "/TE_P$9") (pintype "input"))
      (node (ref "R23") (pin "2") (pinfunction "2_2") (pintype "passive"))
      (node (ref "R25") (pin "2") (pinfunction "2_2") (pintype "passive"))
      (node (ref "R26") (pin "2") (pinfunction "2_2") (pintype "passive"))
      (node (ref "R27") (pin "2") (pinfunction "2_2") (pintype "passive"))
    )
    (net (code "64") (name "unconnected-(IC2-CH4-Pad5)") (class "Default")
      (node (ref "IC2") (pin "5") (pinfunction "CH4_5") (pintype "input"))
    )
    (net (code "65") (name "unconnected-(IC2-CH5-Pad6)") (class "Default")
      (node (ref "IC2") (pin "6") (pinfunction "CH5_6") (pintype "input"))
    )
    (net (code "66") (name "unconnected-(IC2-CH6-Pad7)") (class "Default")
      (node (ref "IC2") (pin "7") (pinfunction "CH6_7") (pintype "input"))
    )
    (net (code "67") (name "unconnected-(IC2-CH7-Pad8)") (class "Default")
      (node (ref "IC2") (pin "8") (pinfunction "CH7_8") (pintype "input"))
    )
    (net (code "68") (name "unconnected-(J1-CE1-Pad26)") (class "Default")
      (node (ref "J1") (pin "26") (pinfunction "CE1_26") (pintype "output"))
    )
    (net (code "69") (name "unconnected-(J1-GP16-Pad36)") (class "Default")
      (node (ref "J1") (pin "36") (pinfunction "GP16_36") (pintype "bidirectional"))
    )
    (net (code "70") (name "unconnected-(J1-GP17-Pad11)") (class "Default")
      (node (ref "J1") (pin "11") (pinfunction "GP17_11") (pintype "bidirectional"))
    )
    (net (code "71") (name "unconnected-(J1-GP18#-Pad12)") (class "Default")
      (node (ref "J1") (pin "12") (pinfunction "GP18#_12") (pintype "bidirectional"))
    )
    (net (code "72") (name "unconnected-(J1-GP19-Pad35)") (class "Default")
      (node (ref "J1") (pin "35") (pinfunction "GP19_35") (pintype "bidirectional"))
    )
    (net (code "73") (name "unconnected-(J1-GP20-Pad38)") (class "Default")
      (node (ref "J1") (pin "38") (pinfunction "GP20_38") (pintype "bidirectional"))
    )
    (net (code "74") (name "unconnected-(J1-GP21-Pad40)") (class "Default")
      (node (ref "J1") (pin "40") (pinfunction "GP21_40") (pintype "bidirectional"))
    )
    (net (code "75") (name "unconnected-(J1-GP23-Pad16)") (class "Default")
      (node (ref "J1") (pin "16") (pinfunction "GP23_16") (pintype "bidirectional"))
    )
    (net (code "76") (name "unconnected-(J1-GP24-Pad18)") (class "Default")
      (node (ref "J1") (pin "18") (pinfunction "GP24_18") (pintype "bidirectional"))
    )
    (net (code "77") (name "unconnected-(J1-GP25-Pad22)") (class "Default")
      (node (ref "J1") (pin "22") (pinfunction "GP25_22") (pintype "bidirectional"))
    )
    (net (code "78") (name "unconnected-(J1-GP26-Pad37)") (class "Default")
      (node (ref "J1") (pin "37") (pinfunction "GP26_37") (pintype "bidirectional"))
    )
    (net (code "79") (name "unconnected-(J1-ID_SC-Pad28)") (class "Default")
      (node (ref "J1") (pin "28") (pinfunction "ID_SC_28") (pintype "bidirectional"))
    )
    (net (code "80") (name "unconnected-(J1-ID_SD-Pad27)") (class "Default")
      (node (ref "J1") (pin "27") (pinfunction "ID_SD_27") (pintype "bidirectional"))
    )
    (net (code "81") (name "unconnected-(J1-SCL-Pad5)") (class "Default")
      (node (ref "J1") (pin "5") (pinfunction "SCL_5") (pintype "bidirectional"))
    )
    (net (code "82") (name "unconnected-(J1-SDA-Pad3)") (class "Default")
      (node (ref "J1") (pin "3") (pinfunction "SDA_3") (pintype "bidirectional"))
    )
    (net (code "83") (name "unconnected-(J2-Pad3)") (class "Default")
      (node (ref "J2") (pin "3") (pinfunction "3_3") (pintype "passive"))
    )
    (net (code "84") (name "unconnected-(J2-Pad4)") (class "Default")
      (node (ref "J2") (pin "4") (pinfunction "4_4") (pintype "passive"))
    )
    (net (code "85") (name "unconnected-(J2-Pad6)") (class "Default")
      (node (ref "J2") (pin "6") (pinfunction "6_6") (pintype "passive"))
    )
    (net (code "86") (name "unconnected-(J3-Pad3)") (class "Default")
      (node (ref "J3") (pin "3") (pinfunction "3_3") (pintype "passive"))
    )
    (net (code "87") (name "unconnected-(J3-Pad4)") (class "Default")
      (node (ref "J3") (pin "4") (pinfunction "4_4") (pintype "passive"))
    )
    (net (code "88") (name "unconnected-(J3-Pad6)") (class "Default")
      (node (ref "J3") (pin "6") (pinfunction "6_6") (pintype "passive"))
    )
    (net (code "89") (name "unconnected-(J4-Pad3)") (class "Default")
      (node (ref "J4") (pin "3") (pinfunction "3_3") (pintype "passive"))
    )
    (net (code "90") (name "unconnected-(J4-Pad4)") (class "Default")
      (node (ref "J4") (pin "4") (pinfunction "4_4") (pintype "passive"))
    )
    (net (code "91") (name "unconnected-(J4-Pad6)") (class "Default")
      (node (ref "J4") (pin "6") (pinfunction "6_6") (pintype "passive"))
    )
    (net (code "92") (name "unconnected-(J5-Pad3)") (class "Default")
      (node (ref "J5") (pin "3") (pinfunction "3_3") (pintype "passive"))
    )
    (net (code "93") (name "unconnected-(J5-Pad4)") (class "Default")
      (node (ref "J5") (pin "4") (pinfunction "4_4") (pintype "passive"))
    )
    (net (code "94") (name "unconnected-(J5-Pad6)") (class "Default")
      (node (ref "J5") (pin "6") (pinfunction "6_6") (pintype "passive"))
    )
    (net (code "95") (name "unconnected-(JP2-Pad4)") (class "Default")
      (node (ref "JP2") (pin "4") (pinfunction "4_4") (pintype "passive"))
    )
    (net (code "96") (name "unconnected-(JP2-Pad6)") (class "Default")
      (node (ref "JP2") (pin "6") (pinfunction "6_6") (pintype "passive"))
    )
    (net (code "97") (name "unconnected-(M1-IRQ-Pad8)") (class "Default")
      (node (ref "M1") (pin "8") (pinfunction "IRQ_8") (pintype "bidirectional"))
    )
  )
)
